# B301.net
KiCad netlist of a schematic drawn in EAGLE
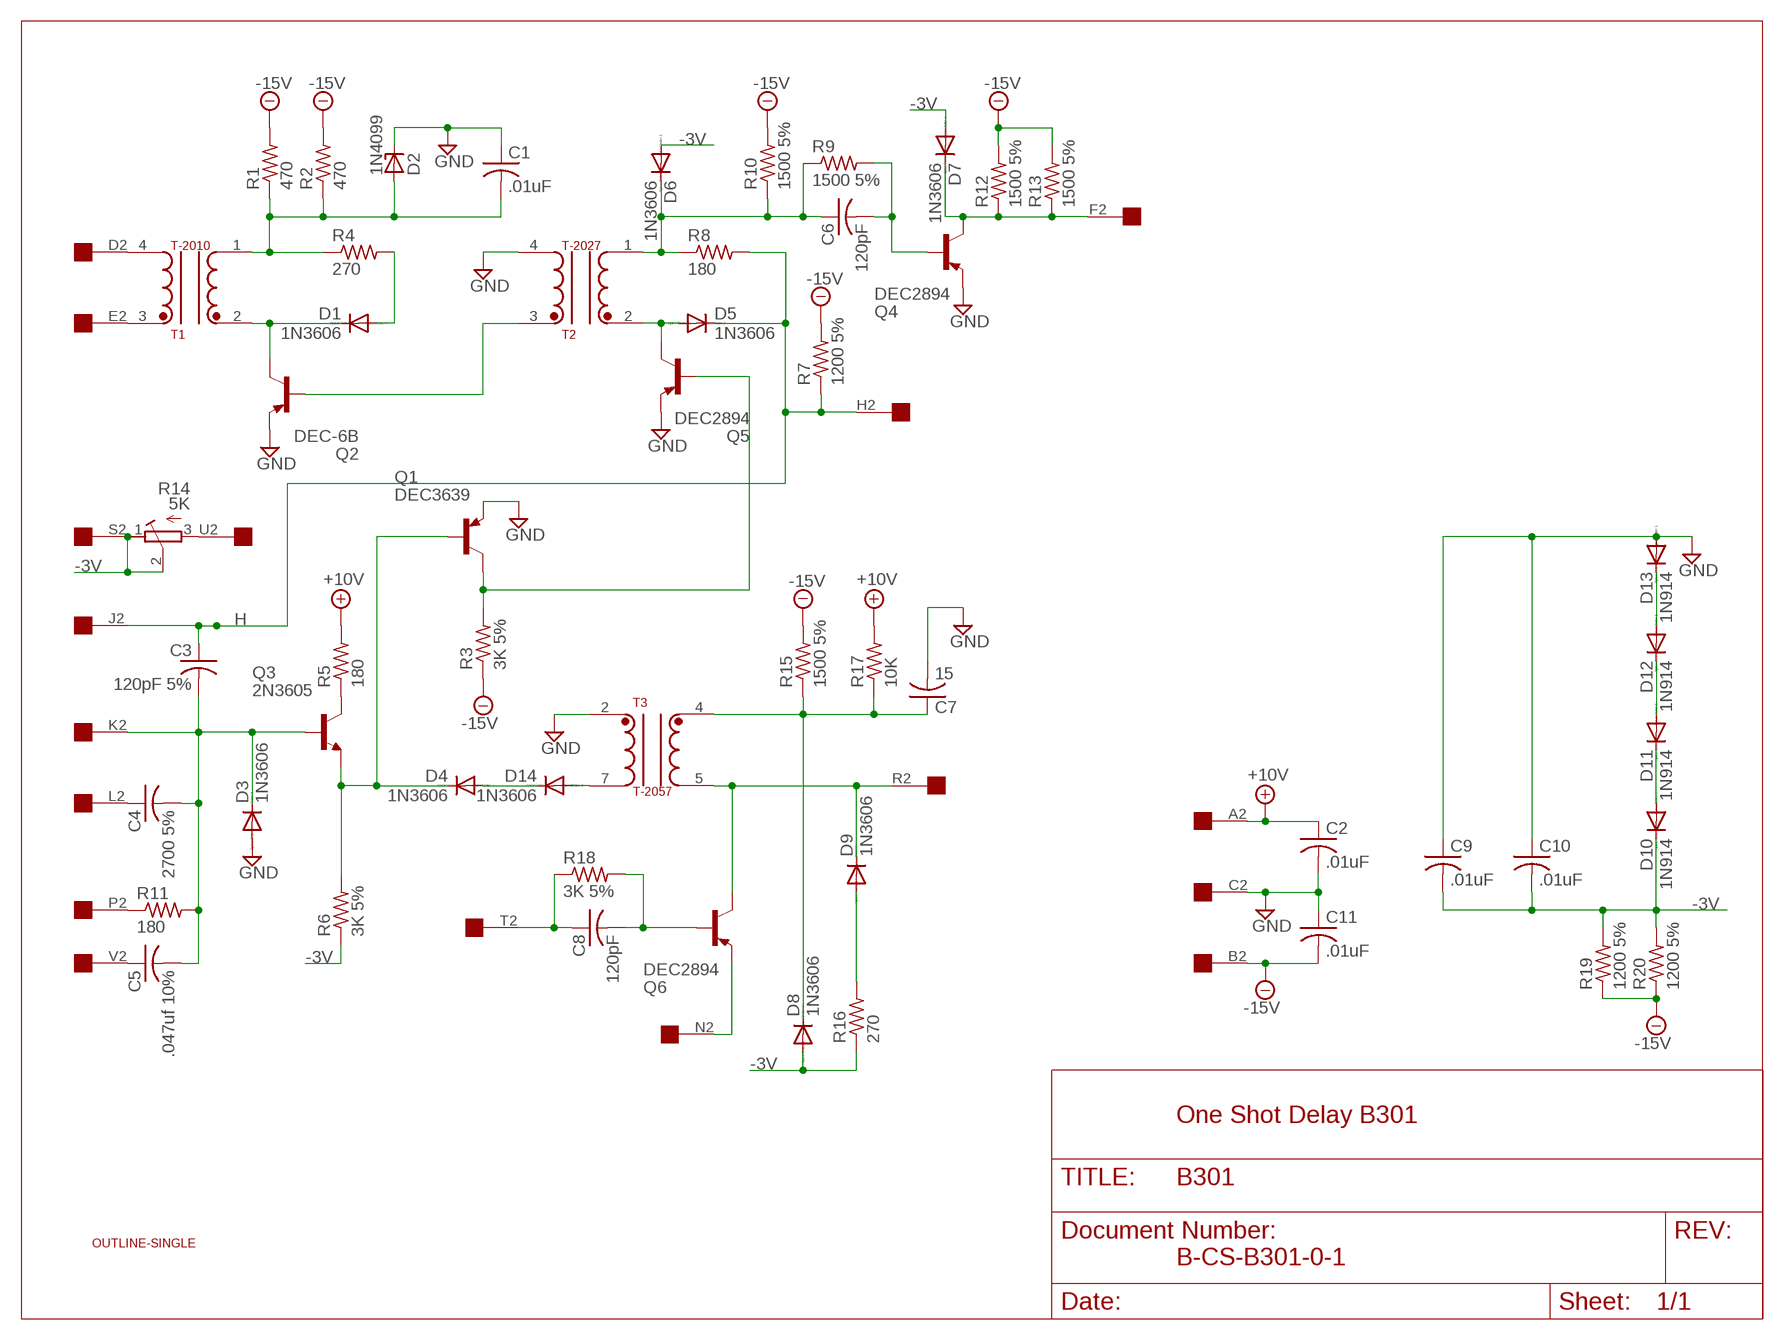
[diagram p0: schematic, sheet 1]

(export (version "E")
  (design (tool "Eeschema 10.0.6"))
  (components
    (comp (ref "C1")
      (value ".01uF")
      (footprint "eagle-import:C050-025X075")
      (libsource (lib "eagle-import") (part "C-US050-025X075"))
    )
    (comp (ref "C2")
      (value ".01uF")
      (footprint "eagle-import:C050-025X075")
      (libsource (lib "eagle-import") (part "C-US050-025X075"))
    )
    (comp (ref "C3")
      (value "120pF 5%")
      (footprint "eagle-import:C050-025X075")
      (libsource (lib "eagle-import") (part "C-US050-025X075"))
    )
    (comp (ref "C4")
      (value "2700 5%")
      (footprint "eagle-import:C102-043X133")
      (libsource (lib "eagle-import") (part "C-US102-043X133"))
    )
    (comp (ref "C5")
      (value ".047uf 10%")
      (footprint "eagle-import:C225-062X268")
      (libsource (lib "eagle-import") (part "C-US225-062X268"))
    )
    (comp (ref "C6")
      (value "120pF")
      (footprint "eagle-import:C050-025X075")
      (libsource (lib "eagle-import") (part "C-US050-025X075"))
    )
    (comp (ref "C7")
      (value "15")
      (footprint "eagle-import:C050-025X075")
      (libsource (lib "eagle-import") (part "C-US050-025X075"))
    )
    (comp (ref "C8")
      (value "120pF")
      (footprint "eagle-import:C050-025X075")
      (libsource (lib "eagle-import") (part "C-US050-025X075"))
    )
    (comp (ref "C9")
      (value ".01uF")
      (footprint "eagle-import:C050-025X075")
      (libsource (lib "eagle-import") (part "C-US050-025X075"))
    )
    (comp (ref "C10")
      (value ".01uF")
      (footprint "eagle-import:C050-025X075")
      (libsource (lib "eagle-import") (part "C-US050-025X075"))
    )
    (comp (ref "C11")
      (value ".01uF")
      (footprint "eagle-import:C050-025X075")
      (libsource (lib "eagle-import") (part "C-US050-025X075"))
    )
    (comp (ref "D1")
      (value "1N3606")
      (footprint "eagle-import:DO35-10")
      (libsource (lib "eagle-import") (part "1N4148DO35-10"))
    )
    (comp (ref "D2")
      (value "1N4099")
      (footprint "eagle-import:DO35Z10")
      (libsource (lib "eagle-import") (part "ZENER-DIODEDO35Z10"))
    )
    (comp (ref "D3")
      (value "1N3606")
      (footprint "eagle-import:DO35-10")
      (libsource (lib "eagle-import") (part "1N4148DO35-10"))
    )
    (comp (ref "D4")
      (value "1N3606")
      (footprint "eagle-import:DO35-10")
      (libsource (lib "eagle-import") (part "1N4148DO35-10"))
    )
    (comp (ref "D5")
      (value "1N3606")
      (footprint "eagle-import:DO35-10")
      (libsource (lib "eagle-import") (part "1N4148DO35-10"))
    )
    (comp (ref "D6")
      (value "1N3606")
      (footprint "eagle-import:DO35-10")
      (libsource (lib "eagle-import") (part "1N4148DO35-10"))
    )
    (comp (ref "D7")
      (value "1N3606")
      (footprint "eagle-import:DO35-10")
      (libsource (lib "eagle-import") (part "1N4148DO35-10"))
    )
    (comp (ref "D8")
      (value "1N3606")
      (footprint "eagle-import:DO35-10")
      (libsource (lib "eagle-import") (part "1N4148DO35-10"))
    )
    (comp (ref "D9")
      (value "1N3606")
      (footprint "eagle-import:DO35-10")
      (libsource (lib "eagle-import") (part "1N4148DO35-10"))
    )
    (comp (ref "D10")
      (value "1N914")
      (footprint "eagle-import:DO35-10")
      (libsource (lib "eagle-import") (part "1N4148DO35-10"))
    )
    (comp (ref "D11")
      (value "1N914")
      (footprint "eagle-import:DO35-10")
      (libsource (lib "eagle-import") (part "1N4148DO35-10"))
    )
    (comp (ref "D12")
      (value "1N914")
      (footprint "eagle-import:DO35-10")
      (libsource (lib "eagle-import") (part "1N4148DO35-10"))
    )
    (comp (ref "D13")
      (value "1N914")
      (footprint "eagle-import:DO35-10")
      (libsource (lib "eagle-import") (part "1N4148DO35-10"))
    )
    (comp (ref "D14")
      (value "1N3606")
      (footprint "eagle-import:DO35-10")
      (libsource (lib "eagle-import") (part "1N4148DO35-10"))
    )
    (comp (ref "Q1")
      (value "DEC3639")
      (footprint "eagle-import:TO39")
      (libsource (lib "eagle-import") (part "2N2904"))
    )
    (comp (ref "Q2")
      (value "DEC-6B")
      (footprint "eagle-import:TO39")
      (libsource (lib "eagle-import") (part "2N2904"))
    )
    (comp (ref "Q3")
      (value "2N3605")
      (footprint "eagle-import:TO39")
      (libsource (lib "eagle-import") (part "-NPN-TO39-EBC2N2102"))
    )
    (comp (ref "Q4")
      (value "DEC2894")
      (footprint "eagle-import:TO39")
      (libsource (lib "eagle-import") (part "2N2904"))
    )
    (comp (ref "Q5")
      (value "DEC2894")
      (footprint "eagle-import:TO39")
      (libsource (lib "eagle-import") (part "2N2904"))
    )
    (comp (ref "Q6")
      (value "DEC2894")
      (footprint "eagle-import:TO39")
      (libsource (lib "eagle-import") (part "2N2904"))
    )
    (comp (ref "R1")
      (value "470")
      (footprint "eagle-import:0207_10")
      (libsource (lib "eagle-import") (part "R-US_0207/10"))
    )
    (comp (ref "R2")
      (value "470")
      (footprint "eagle-import:0207_10")
      (libsource (lib "eagle-import") (part "R-US_0207/10"))
    )
    (comp (ref "R3")
      (value "3K 5%")
      (footprint "eagle-import:0207_10")
      (libsource (lib "eagle-import") (part "R-US_0207/10"))
    )
    (comp (ref "R4")
      (value "270")
      (footprint "eagle-import:0207_10")
      (libsource (lib "eagle-import") (part "R-US_0207/10"))
    )
    (comp (ref "R5")
      (value "180")
      (footprint "eagle-import:0207_10")
      (libsource (lib "eagle-import") (part "R-US_0207/10"))
    )
    (comp (ref "R6")
      (value "3K 5%")
      (footprint "eagle-import:0207_10")
      (libsource (lib "eagle-import") (part "R-US_0207/10"))
    )
    (comp (ref "R7")
      (value "1200 5%")
      (footprint "eagle-import:0207_10")
      (libsource (lib "eagle-import") (part "R-US_0207/10"))
    )
    (comp (ref "R8")
      (value "180")
      (footprint "eagle-import:0207_10")
      (libsource (lib "eagle-import") (part "R-US_0207/10"))
    )
    (comp (ref "R9")
      (value "1500 5%")
      (footprint "eagle-import:0207_10")
      (libsource (lib "eagle-import") (part "R-US_0207/10"))
    )
    (comp (ref "R10")
      (value "1500 5%")
      (footprint "eagle-import:0207_10")
      (libsource (lib "eagle-import") (part "R-US_0207/10"))
    )
    (comp (ref "R11")
      (value "180")
      (footprint "eagle-import:0207_10")
      (libsource (lib "eagle-import") (part "R-US_0207/10"))
    )
    (comp (ref "R12")
      (value "1500 5%")
      (footprint "eagle-import:0207_10")
      (libsource (lib "eagle-import") (part "R-US_0207/10"))
    )
    (comp (ref "R13")
      (value "1500 5%")
      (footprint "eagle-import:0207_10")
      (libsource (lib "eagle-import") (part "R-US_0207/10"))
    )
    (comp (ref "R14")
      (value "5K")
      (footprint "eagle-import:3006Y")
      (libsource (lib "eagle-import") (part "275P"))
    )
    (comp (ref "R15")
      (value "1500 5%")
      (footprint "eagle-import:0207_10")
      (libsource (lib "eagle-import") (part "R-US_0207/10"))
    )
    (comp (ref "R16")
      (value "270")
      (footprint "eagle-import:0207_10")
      (libsource (lib "eagle-import") (part "R-US_0207/10"))
    )
    (comp (ref "R17")
      (value "10K")
      (footprint "eagle-import:0207_10")
      (libsource (lib "eagle-import") (part "R-US_0207/10"))
    )
    (comp (ref "R18")
      (value "3K 5%")
      (footprint "eagle-import:0207_10")
      (libsource (lib "eagle-import") (part "R-US_0207/10"))
    )
    (comp (ref "R19")
      (value "1200 5%")
      (footprint "eagle-import:0207_10")
      (libsource (lib "eagle-import") (part "R-US_0207/10"))
    )
    (comp (ref "R20")
      (value "1200 5%")
      (footprint "eagle-import:0207_10")
      (libsource (lib "eagle-import") (part "R-US_0207/10"))
    )
    (comp (ref "T1")
      (value "T-2010")
      (footprint "eagle-import:TRANSFORMER2")
      (libsource (lib "eagle-import") (part "T-2010"))
    )
    (comp (ref "T2")
      (value "T-2027")
      (footprint "eagle-import:TRANSFORMER2")
      (libsource (lib "eagle-import") (part "T-2010"))
    )
    (comp (ref "T3")
      (value "T-2057")
      (footprint "eagle-import:TRANSFORMER")
      (libsource (lib "eagle-import") (part "T-2037"))
    )
    (comp (ref "U$1")
      (value "OUTLINE-SINGLE")
      (footprint "eagle-import:SINGLE")
      (libsource (lib "eagle-import") (part "OUTLINE-SINGLE"))
    )
    (comp (ref "U$2")
      (value "EDGE-1")
      (footprint "eagle-import:EDGE-CON1")
      (libsource (lib "eagle-import") (part "EDGE-1"))
    )
  )
  (nets
    (net (code "1") (name "+10V") (class "Default")
      (node (ref "C2") (pin "1") (pinfunction "1_1") (pintype "passive"))
      (node (ref "R17") (pin "2") (pinfunction "2_2") (pintype "passive"))
      (node (ref "R5") (pin "2") (pinfunction "2_2") (pintype "passive"))
      (node (ref "U$2") (pin "A2") (pinfunction "1_A2") (pintype "bidirectional"))
    )
    (net (code "2") (name "-15V") (class "Default")
      (node (ref "C11") (pin "2") (pinfunction "2_2") (pintype "passive"))
      (node (ref "R1") (pin "2") (pinfunction "2_2") (pintype "passive"))
      (node (ref "R10") (pin "2") (pinfunction "2_2") (pintype "passive"))
      (node (ref "R12") (pin "2") (pinfunction "2_2") (pintype "passive"))
      (node (ref "R13") (pin "2") (pinfunction "2_2") (pintype "passive"))
      (node (ref "R15") (pin "2") (pinfunction "2_2") (pintype "passive"))
      (node (ref "R19") (pin "1") (pinfunction "1_1") (pintype "passive"))
      (node (ref "R2") (pin "2") (pinfunction "2_2") (pintype "passive"))
      (node (ref "R20") (pin "1") (pinfunction "1_1") (pintype "passive"))
      (node (ref "R3") (pin "1") (pinfunction "1_1") (pintype "passive"))
      (node (ref "R7") (pin "2") (pinfunction "2_2") (pintype "passive"))
      (node (ref "U$2") (pin "B2") (pinfunction "1_B2") (pintype "bidirectional"))
    )
    (net (code "3") (name "/-3V") (class "Default")
      (node (ref "C10") (pin "2") (pinfunction "2_2") (pintype "passive"))
      (node (ref "C9") (pin "2") (pinfunction "2_2") (pintype "passive"))
      (node (ref "D10") (pin "C") (pinfunction "C_C") (pintype "passive"))
      (node (ref "D6") (pin "A") (pinfunction "A_A") (pintype "passive"))
      (node (ref "D7") (pin "A") (pinfunction "A_A") (pintype "passive"))
      (node (ref "D8") (pin "A") (pinfunction "A_A") (pintype "passive"))
      (node (ref "R14") (pin "1") (pinfunction "A_1") (pintype "passive"))
      (node (ref "R14") (pin "2") (pinfunction "S_2") (pintype "passive"))
      (node (ref "R16") (pin "1") (pinfunction "1_1") (pintype "passive"))
      (node (ref "R19") (pin "2") (pinfunction "2_2") (pintype "passive"))
      (node (ref "R20") (pin "2") (pinfunction "2_2") (pintype "passive"))
      (node (ref "R6") (pin "1") (pinfunction "1_1") (pintype "passive"))
      (node (ref "U$2") (pin "S2") (pinfunction "1_S2") (pintype "bidirectional"))
    )
    (net (code "4") (name "/H") (class "Default")
      (node (ref "C3") (pin "1") (pinfunction "1_1") (pintype "passive"))
      (node (ref "D5") (pin "C") (pinfunction "C_C") (pintype "passive"))
      (node (ref "R7") (pin "1") (pinfunction "1_1") (pintype "passive"))
      (node (ref "R8") (pin "2") (pinfunction "2_2") (pintype "passive"))
      (node (ref "U$2") (pin "H2") (pinfunction "1_H2") (pintype "bidirectional"))
      (node (ref "U$2") (pin "J2") (pinfunction "1_J2") (pintype "bidirectional"))
    )
    (net (code "5") (name "GND") (class "Default")
      (node (ref "C1") (pin "1") (pinfunction "1_1") (pintype "passive"))
      (node (ref "C10") (pin "1") (pinfunction "1_1") (pintype "passive"))
      (node (ref "C11") (pin "1") (pinfunction "1_1") (pintype "passive"))
      (node (ref "C2") (pin "2") (pinfunction "2_2") (pintype "passive"))
      (node (ref "C7") (pin "2") (pinfunction "2_2") (pintype "passive"))
      (node (ref "C9") (pin "1") (pinfunction "1_1") (pintype "passive"))
      (node (ref "D13") (pin "A") (pinfunction "A_A") (pintype "passive"))
      (node (ref "D2") (pin "C") (pinfunction "C_C") (pintype "passive"))
      (node (ref "D3") (pin "A") (pinfunction "A_A") (pintype "passive"))
      (node (ref "Q1") (pin "1") (pinfunction "E_1") (pintype "passive"))
      (node (ref "Q2") (pin "1") (pinfunction "E_1") (pintype "passive"))
      (node (ref "Q4") (pin "1") (pinfunction "E_1") (pintype "passive"))
      (node (ref "Q5") (pin "1") (pinfunction "E_1") (pintype "passive"))
      (node (ref "T2") (pin "4") (pinfunction "P$7_4") (pintype "passive"))
      (node (ref "T3") (pin "2") (pinfunction "P$2_2") (pintype "passive"))
      (node (ref "U$2") (pin "C2") (pinfunction "1_C2") (pintype "bidirectional"))
    )
    (net (code "6") (name "Net-(D1-PadA)") (class "Default")
      (node (ref "D1") (pin "A") (pinfunction "A_A") (pintype "passive"))
      (node (ref "R4") (pin "2") (pinfunction "2_2") (pintype "passive"))
    )
    (net (code "7") (name "Net-(D9-PadA)") (class "Default")
      (node (ref "D9") (pin "A") (pinfunction "A_A") (pintype "passive"))
      (node (ref "R16") (pin "2") (pinfunction "2_2") (pintype "passive"))
    )
    (net (code "8") (name "Net-(D10-PadA)") (class "Default")
      (node (ref "D10") (pin "A") (pinfunction "A_A") (pintype "passive"))
      (node (ref "D11") (pin "C") (pinfunction "C_C") (pintype "passive"))
    )
    (net (code "9") (name "Net-(D11-PadA)") (class "Default")
      (node (ref "D11") (pin "A") (pinfunction "A_A") (pintype "passive"))
      (node (ref "D12") (pin "C") (pinfunction "C_C") (pintype "passive"))
    )
    (net (code "10") (name "Net-(D12-PadA)") (class "Default")
      (node (ref "D12") (pin "A") (pinfunction "A_A") (pintype "passive"))
      (node (ref "D13") (pin "C") (pinfunction "C_C") (pintype "passive"))
    )
    (net (code "11") (name "Net-(D14-PadC)") (class "Default")
      (node (ref "D14") (pin "C") (pinfunction "C_C") (pintype "passive"))
      (node (ref "D4") (pin "A") (pinfunction "A_A") (pintype "passive"))
    )
    (net (code "12") (name "Net-(Q1-B)") (class "Default")
      (node (ref "D4") (pin "C") (pinfunction "C_C") (pintype "passive"))
      (node (ref "Q1") (pin "2") (pinfunction "B_2") (pintype "passive"))
      (node (ref "Q3") (pin "1") (pinfunction "E_1") (pintype "passive"))
      (node (ref "R6") (pin "2") (pinfunction "2_2") (pintype "passive"))
    )
    (net (code "13") (name "Net-(Q1-C)") (class "Default")
      (node (ref "Q1") (pin "3") (pinfunction "C_3") (pintype "passive"))
      (node (ref "Q5") (pin "2") (pinfunction "B_2") (pintype "passive"))
      (node (ref "R3") (pin "2") (pinfunction "2_2") (pintype "passive"))
    )
    (net (code "14") (name "Net-(Q2-B)") (class "Default")
      (node (ref "Q2") (pin "2") (pinfunction "B_2") (pintype "passive"))
      (node (ref "T2") (pin "3") (pinfunction "P$2_3") (pintype "passive"))
    )
    (net (code "15") (name "Net-(Q2-C)") (class "Default")
      (node (ref "D1") (pin "C") (pinfunction "C_C") (pintype "passive"))
      (node (ref "Q2") (pin "3") (pinfunction "C_3") (pintype "passive"))
      (node (ref "T1") (pin "2") (pinfunction "P$4_2") (pintype "passive"))
    )
    (net (code "16") (name "Net-(Q3-B)") (class "Default")
      (node (ref "C3") (pin "2") (pinfunction "2_2") (pintype "passive"))
      (node (ref "C4") (pin "2") (pinfunction "2_2") (pintype "passive"))
      (node (ref "C5") (pin "2") (pinfunction "2_2") (pintype "passive"))
      (node (ref "D3") (pin "C") (pinfunction "C_C") (pintype "passive"))
      (node (ref "Q3") (pin "2") (pinfunction "B_2") (pintype "passive"))
      (node (ref "R11") (pin "2") (pinfunction "2_2") (pintype "passive"))
      (node (ref "U$2") (pin "K2") (pinfunction "1_K2") (pintype "bidirectional"))
    )
    (net (code "17") (name "Net-(Q3-C)") (class "Default")
      (node (ref "Q3") (pin "3") (pinfunction "C_3") (pintype "passive"))
      (node (ref "R5") (pin "1") (pinfunction "1_1") (pintype "passive"))
    )
    (net (code "18") (name "Net-(Q4-B)") (class "Default")
      (node (ref "C6") (pin "2") (pinfunction "2_2") (pintype "passive"))
      (node (ref "Q4") (pin "2") (pinfunction "B_2") (pintype "passive"))
      (node (ref "R9") (pin "2") (pinfunction "2_2") (pintype "passive"))
    )
    (net (code "19") (name "Net-(Q4-C)") (class "Default")
      (node (ref "D7") (pin "C") (pinfunction "C_C") (pintype "passive"))
      (node (ref "Q4") (pin "3") (pinfunction "C_3") (pintype "passive"))
      (node (ref "R12") (pin "1") (pinfunction "1_1") (pintype "passive"))
      (node (ref "R13") (pin "1") (pinfunction "1_1") (pintype "passive"))
      (node (ref "U$2") (pin "F2") (pinfunction "1_F2") (pintype "bidirectional"))
    )
    (net (code "20") (name "Net-(Q5-C)") (class "Default")
      (node (ref "D5") (pin "A") (pinfunction "A_A") (pintype "passive"))
      (node (ref "Q5") (pin "3") (pinfunction "C_3") (pintype "passive"))
      (node (ref "T2") (pin "2") (pinfunction "P$4_2") (pintype "passive"))
    )
    (net (code "21") (name "Net-(Q6-B)") (class "Default")
      (node (ref "C8") (pin "2") (pinfunction "2_2") (pintype "passive"))
      (node (ref "Q6") (pin "2") (pinfunction "B_2") (pintype "passive"))
      (node (ref "R18") (pin "2") (pinfunction "2_2") (pintype "passive"))
    )
    (net (code "22") (name "Net-(Q6-C)") (class "Default")
      (node (ref "D9") (pin "C") (pinfunction "C_C") (pintype "passive"))
      (node (ref "Q6") (pin "3") (pinfunction "C_3") (pintype "passive"))
      (node (ref "T3") (pin "5") (pinfunction "P$5_5") (pintype "passive"))
      (node (ref "U$2") (pin "R2") (pinfunction "1_R2") (pintype "bidirectional"))
    )
    (net (code "23") (name "Net-(Q6-E)") (class "Default")
      (node (ref "Q6") (pin "1") (pinfunction "E_1") (pintype "passive"))
      (node (ref "U$2") (pin "N2") (pinfunction "1_N2") (pintype "bidirectional"))
    )
    (net (code "24") (name "Net-(R14-E)") (class "Default")
      (node (ref "R14") (pin "3") (pinfunction "E_3") (pintype "passive"))
      (node (ref "U$2") (pin "U2") (pinfunction "1_U2") (pintype "bidirectional"))
    )
    (net (code "25") (name "Net-(T1-P$2)") (class "Default")
      (node (ref "T1") (pin "3") (pinfunction "P$2_3") (pintype "passive"))
      (node (ref "U$2") (pin "E2") (pinfunction "1_E2") (pintype "bidirectional"))
    )
    (net (code "26") (name "Net-(T1-P$5)") (class "Default")
      (node (ref "C1") (pin "2") (pinfunction "2_2") (pintype "passive"))
      (node (ref "D2") (pin "A") (pinfunction "A_A") (pintype "passive"))
      (node (ref "R1") (pin "1") (pinfunction "1_1") (pintype "passive"))
      (node (ref "R2") (pin "1") (pinfunction "1_1") (pintype "passive"))
      (node (ref "R4") (pin "1") (pinfunction "1_1") (pintype "passive"))
      (node (ref "T1") (pin "1") (pinfunction "P$5_1") (pintype "passive"))
    )
    (net (code "27") (name "Net-(T1-P$7)") (class "Default")
      (node (ref "T1") (pin "4") (pinfunction "P$7_4") (pintype "passive"))
      (node (ref "U$2") (pin "D2") (pinfunction "1_D2") (pintype "bidirectional"))
    )
    (net (code "28") (name "Net-(T2-P$5)") (class "Default")
      (node (ref "C6") (pin "1") (pinfunction "1_1") (pintype "passive"))
      (node (ref "D6") (pin "C") (pinfunction "C_C") (pintype "passive"))
      (node (ref "R10") (pin "1") (pinfunction "1_1") (pintype "passive"))
      (node (ref "R8") (pin "1") (pinfunction "1_1") (pintype "passive"))
      (node (ref "R9") (pin "1") (pinfunction "1_1") (pintype "passive"))
      (node (ref "T2") (pin "1") (pinfunction "P$5_1") (pintype "passive"))
    )
    (net (code "29") (name "Net-(T3-P$4)") (class "Default")
      (node (ref "C7") (pin "1") (pinfunction "1_1") (pintype "passive"))
      (node (ref "D8") (pin "C") (pinfunction "C_C") (pintype "passive"))
      (node (ref "R15") (pin "1") (pinfunction "1_1") (pintype "passive"))
      (node (ref "R17") (pin "1") (pinfunction "1_1") (pintype "passive"))
      (node (ref "T3") (pin "4") (pinfunction "P$4_4") (pintype "passive"))
    )
    (net (code "30") (name "Net-(T3-P$7)") (class "Default")
      (node (ref "D14") (pin "A") (pinfunction "A_A") (pintype "passive"))
      (node (ref "T3") (pin "7") (pinfunction "P$7_7") (pintype "passive"))
    )
    (net (code "31") (name "Net-(U$2J-1)") (class "Default")
      (node (ref "C4") (pin "1") (pinfunction "1_1") (pintype "passive"))
      (node (ref "U$2") (pin "L2") (pinfunction "1_L2") (pintype "bidirectional"))
    )
    (net (code "32") (name "Net-(U$2M-1)") (class "Default")
      (node (ref "R11") (pin "1") (pinfunction "1_1") (pintype "passive"))
      (node (ref "U$2") (pin "P2") (pinfunction "1_P2") (pintype "bidirectional"))
    )
    (net (code "33") (name "Net-(U$2P-1)") (class "Default")
      (node (ref "C8") (pin "1") (pinfunction "1_1") (pintype "passive"))
      (node (ref "R18") (pin "1") (pinfunction "1_1") (pintype "passive"))
      (node (ref "U$2") (pin "T2") (pinfunction "1_T2") (pintype "bidirectional"))
    )
    (net (code "34") (name "Net-(U$2R-1)") (class "Default")
      (node (ref "C5") (pin "1") (pinfunction "1_1") (pintype "passive"))
      (node (ref "U$2") (pin "V2") (pinfunction "1_V2") (pintype "bidirectional"))
    )
  )
)
